# 0SC_praca_mgr.net
KiCad netlist of a schematic drawn in Altium Designer
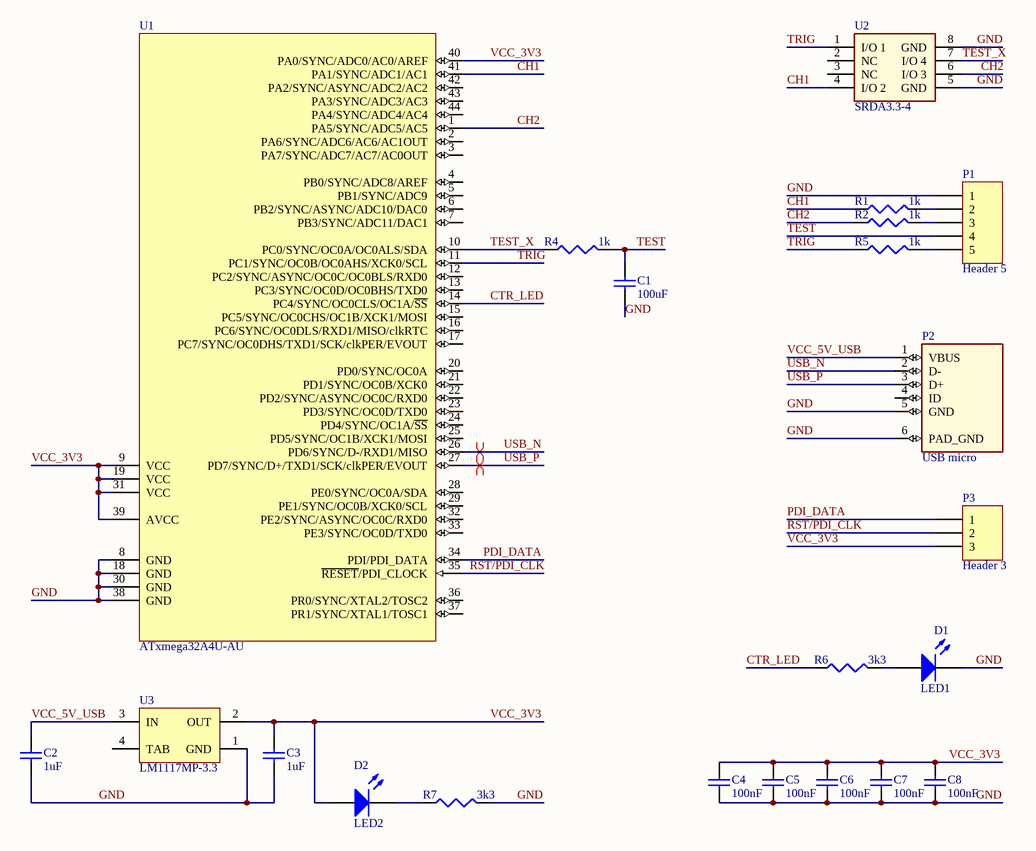
[diagram p0: 0SC_praca_mgr.SchDoc]

(export (version "E")
  (design (tool "Eeschema 10.0.6"))
  (components
    (comp (ref "C1")
      (value "100uF")
      (footprint "1608[0603]")
      (description "Capacitor (Semiconductor SIM Model)")
      (fields (field (name "Comment") "Cap Semi") (field (name "PUBLISHER") "Altium Limited"))
      (libsource (lib "Miscellaneous Devices") (part "Cap Semi"))
    )
    (comp (ref "C2")
      (value "1uF")
      (footprint "1608[0603]")
      (description "Capacitor (Semiconductor SIM Model)")
      (fields (field (name "Comment") "Cap Semi") (field (name "PUBLISHER") "Altium Limited"))
      (libsource (lib "Miscellaneous Devices") (part "Cap Semi"))
    )
    (comp (ref "C3")
      (value "1uF")
      (footprint "1608[0603]")
      (description "Capacitor (Semiconductor SIM Model)")
      (fields (field (name "Comment") "Cap Semi") (field (name "PUBLISHER") "Altium Limited"))
      (libsource (lib "Miscellaneous Devices") (part "Cap Semi"))
    )
    (comp (ref "C4")
      (value "100nF")
      (footprint "1608[0603]")
      (description "Capacitor (Semiconductor SIM Model)")
      (fields (field (name "Comment") "Cap Semi") (field (name "PUBLISHER") "Altium Limited"))
      (libsource (lib "Miscellaneous Devices") (part "Cap Semi"))
    )
    (comp (ref "C5")
      (value "100nF")
      (footprint "1608[0603]")
      (description "Capacitor (Semiconductor SIM Model)")
      (fields (field (name "Comment") "Cap Semi") (field (name "PUBLISHER") "Altium Limited"))
      (libsource (lib "Miscellaneous Devices") (part "Cap Semi"))
    )
    (comp (ref "C6")
      (value "100nF")
      (footprint "1608[0603]")
      (description "Capacitor (Semiconductor SIM Model)")
      (fields (field (name "Comment") "Cap Semi") (field (name "PUBLISHER") "Altium Limited"))
      (libsource (lib "Miscellaneous Devices") (part "Cap Semi"))
    )
    (comp (ref "C7")
      (value "100nF")
      (footprint "1608[0603]")
      (description "Capacitor (Semiconductor SIM Model)")
      (fields (field (name "Comment") "Cap Semi") (field (name "PUBLISHER") "Altium Limited"))
      (libsource (lib "Miscellaneous Devices") (part "Cap Semi"))
    )
    (comp (ref "C8")
      (value "100nF")
      (footprint "1608[0603]")
      (description "Capacitor (Semiconductor SIM Model)")
      (fields (field (name "Comment") "Cap Semi") (field (name "PUBLISHER") "Altium Limited"))
      (libsource (lib "Miscellaneous Devices") (part "Cap Semi"))
    )
    (comp (ref "D1") (value "LED1") (footprint "0603_led") (libsource (lib "Osc_praca_mgr_lib") (part "Led")))
    (comp (ref "D2") (value "LED2") (footprint "0603_led") (libsource (lib "Osc_praca_mgr_lib") (part "Led")))
    (comp (ref "P1")
      (value "Header 5")
      (footprint "HDR1X5")
      (description "Header, 5-Pin")
      (fields (field (name "PUBLISHER") "Altium Limited"))
      (libsource (lib "Miscellaneous Connectors") (part "Header 5"))
    )
    (comp (ref "P2")
      (value "USB micro")
      (footprint "KEY-940")
      (libsource (lib "Osc_praca_mgr_lib") (part "USB micro"))
    )
    (comp (ref "P3")
      (value "Header 3")
      (footprint "HDR1X3")
      (description "Header, 3-Pin")
      (fields (field (name "PUBLISHER") "Altium Limited"))
      (libsource (lib "Miscellaneous Connectors") (part "Header 3"))
    )
    (comp (ref "R1")
      (value "1k")
      (footprint "J1-0603")
      (description "Resistor")
      (fields (field (name "Comment") "Res3") (field (name "PUBLISHER") "Altium Limited"))
      (libsource (lib "Miscellaneous Devices") (part "Res3"))
    )
    (comp (ref "R2")
      (value "1k")
      (footprint "J1-0603")
      (description "Resistor")
      (fields (field (name "Comment") "Res3") (field (name "PUBLISHER") "Altium Limited"))
      (libsource (lib "Miscellaneous Devices") (part "Res3"))
    )
    (comp (ref "R4")
      (value "1k")
      (footprint "J1-0603")
      (description "Resistor")
      (fields (field (name "Comment") "Res3") (field (name "PUBLISHER") "Altium Limited"))
      (libsource (lib "Miscellaneous Devices") (part "Res3"))
    )
    (comp (ref "R5")
      (value "1k")
      (footprint "J1-0603")
      (description "Resistor")
      (fields (field (name "Comment") "Res3") (field (name "PUBLISHER") "Altium Limited"))
      (libsource (lib "Miscellaneous Devices") (part "Res3"))
    )
    (comp (ref "R6")
      (value "3k3")
      (footprint "J1-0603")
      (description "Resistor")
      (fields (field (name "Comment") "Res3") (field (name "PUBLISHER") "Altium Limited"))
      (libsource (lib "Miscellaneous Devices") (part "Res3"))
    )
    (comp (ref "R7")
      (value "3k3")
      (footprint "J1-0603")
      (description "Resistor")
      (fields (field (name "Comment") "Res3") (field (name "PUBLISHER") "Altium Limited"))
      (libsource (lib "Miscellaneous Devices") (part "Res3"))
    )
    (comp (ref "U1")
      (value "ATxmega32A4U-AU")
      (footprint "44A_N")
      (libsource (lib "Atmel Microcontroller AVR XMEGA") (part "ATxmega32A4U-AU"))
    )
    (comp (ref "U2")
      (value "SRDA3.3-4")
      (footprint "SOIC8")
      (libsource (lib "Osc_praca_mgr_lib") (part "SRDA3.3-4"))
    )
    (comp (ref "U3")
      (value "LM1117MP-3.3")
      (footprint "MP04A_N")
      (description "800mA Low-Dropout Linear Regulator")
      (fields
        (field (name "MANUFACTURER") "National Semiconductor")
        (field (name "DIGIKEYPARTNUMBER") "LM1117MP-3.3CT-ND")
        (field (name "PUBLISHER") "Altium Limited")
      )
      (libsource (lib "NSC LDO") (part "LM1117MP-3.3"))
    )
  )
  (nets
    (net (code "1") (name "/CH1") (class "Default")
      (node (ref "R1") (pin "1") (pinfunction "1_1") (pintype "passive"))
      (node (ref "U1") (pin "41") (pinfunction "PA1/SYNC/ADC1/AC1_41") (pintype "bidirectional"))
      (node (ref "U2") (pin "4") (pinfunction "I/O_2_4") (pintype "passive"))
    )
    (net (code "2") (name "/CH2") (class "Default")
      (node (ref "R2") (pin "1") (pinfunction "1_1") (pintype "passive"))
      (node (ref "U1") (pin "1") (pinfunction "PA5/SYNC/ADC5/AC5_1") (pintype "bidirectional"))
      (node (ref "U2") (pin "6") (pinfunction "I/O_3_6") (pintype "passive"))
    )
    (net (code "3") (name "/CTR_LED") (class "Default")
      (node (ref "R6") (pin "1") (pinfunction "1_1") (pintype "passive"))
      (node (ref "U1") (pin "14") (pinfunction "PC4/SYNC/OC0CLS/OC1A/~{SS}_14") (pintype "bidirectional"))
    )
    (net (code "4") (name "/GND") (class "Default")
      (node (ref "C1") (pin "1") (pinfunction "1_1") (pintype "passive"))
      (node (ref "C2") (pin "1") (pinfunction "1_1") (pintype "passive"))
      (node (ref "C3") (pin "1") (pinfunction "1_1") (pintype "passive"))
      (node (ref "C4") (pin "1") (pinfunction "1_1") (pintype "passive"))
      (node (ref "C5") (pin "1") (pinfunction "1_1") (pintype "passive"))
      (node (ref "C6") (pin "1") (pinfunction "1_1") (pintype "passive"))
      (node (ref "C7") (pin "1") (pinfunction "1_1") (pintype "passive"))
      (node (ref "C8") (pin "1") (pinfunction "1_1") (pintype "passive"))
      (node (ref "D1") (pin "2") (pinfunction "K_2") (pintype "passive"))
      (node (ref "P1") (pin "1") (pinfunction "1_1") (pintype "passive"))
      (node (ref "P2") (pin "5") (pinfunction "GND_5") (pintype "bidirectional"))
      (node (ref "P2") (pin "6") (pinfunction "PAD_GND_6") (pintype "bidirectional"))
      (node (ref "R7") (pin "2") (pinfunction "2_2") (pintype "passive"))
      (node (ref "U1") (pin "18") (pinfunction "GND_18") (pintype "power_in"))
      (node (ref "U1") (pin "30") (pinfunction "GND_30") (pintype "power_in"))
      (node (ref "U1") (pin "38") (pinfunction "GND_38") (pintype "power_in"))
      (node (ref "U1") (pin "8") (pinfunction "GND_8") (pintype "power_in"))
      (node (ref "U2") (pin "5") (pinfunction "GND_5") (pintype "passive"))
      (node (ref "U2") (pin "8") (pinfunction "GND_8") (pintype "passive"))
      (node (ref "U3") (pin "1") (pinfunction "GND_1") (pintype "power_in"))
    )
    (net (code "5") (name "/PDI_DATA") (class "Default")
      (node (ref "P3") (pin "1") (pinfunction "1_1") (pintype "passive"))
      (node (ref "U1") (pin "34") (pinfunction "PDI/PDI_DATA_34") (pintype "bidirectional"))
    )
    (net (code "6") (name "/TEST") (class "Default")
      (node (ref "C1") (pin "2") (pinfunction "2_2") (pintype "passive"))
      (node (ref "P1") (pin "4") (pinfunction "4_4") (pintype "passive"))
      (node (ref "R4") (pin "2") (pinfunction "2_2") (pintype "passive"))
    )
    (net (code "7") (name "/TEST_X") (class "Default")
      (node (ref "R4") (pin "1") (pinfunction "1_1") (pintype "passive"))
      (node (ref "U1") (pin "10") (pinfunction "PC0/SYNC/OC0A/OC0ALS/SDA_10") (pintype "bidirectional"))
      (node (ref "U2") (pin "7") (pinfunction "I/O_4_7") (pintype "passive"))
    )
    (net (code "8") (name "/TRIG") (class "Default")
      (node (ref "R5") (pin "1") (pinfunction "1_1") (pintype "passive"))
      (node (ref "U1") (pin "11") (pinfunction "PC1/SYNC/OC0B/OC0AHS/XCK0/SCL_11") (pintype "bidirectional"))
      (node (ref "U2") (pin "1") (pinfunction "I/O_1_1") (pintype "passive"))
    )
    (net (code "9") (name "/USB_N") (class "Default")
      (node (ref "P2") (pin "2") (pinfunction "D-_2") (pintype "bidirectional"))
      (node (ref "U1") (pin "26") (pinfunction "PD6/SYNC/D-/RXD1/MISO_26") (pintype "bidirectional"))
    )
    (net (code "10") (name "/USB_P") (class "Default")
      (node (ref "P2") (pin "3") (pinfunction "D+_3") (pintype "bidirectional"))
      (node (ref "U1") (pin "27") (pinfunction "PD7/SYNC/D+/TXD1/SCK/clkPER/EVOUT_27") (pintype "bidirectional"))
    )
    (net (code "11") (name "/VCC_3V3") (class "Default")
      (node (ref "C3") (pin "2") (pinfunction "2_2") (pintype "passive"))
      (node (ref "C4") (pin "2") (pinfunction "2_2") (pintype "passive"))
      (node (ref "C5") (pin "2") (pinfunction "2_2") (pintype "passive"))
      (node (ref "C6") (pin "2") (pinfunction "2_2") (pintype "passive"))
      (node (ref "C7") (pin "2") (pinfunction "2_2") (pintype "passive"))
      (node (ref "C8") (pin "2") (pinfunction "2_2") (pintype "passive"))
      (node (ref "D2") (pin "1") (pinfunction "A_1") (pintype "passive"))
      (node (ref "P3") (pin "3") (pinfunction "3_3") (pintype "passive"))
      (node (ref "U1") (pin "19") (pinfunction "VCC_19") (pintype "power_in"))
      (node (ref "U1") (pin "31") (pinfunction "VCC_31") (pintype "power_in"))
      (node (ref "U1") (pin "39") (pinfunction "AVCC_39") (pintype "power_in"))
      (node (ref "U1") (pin "40") (pinfunction "PA0/SYNC/ADC0/AC0/AREF_40") (pintype "bidirectional"))
      (node (ref "U1") (pin "9") (pinfunction "VCC_9") (pintype "power_in"))
      (node (ref "U3") (pin "2") (pinfunction "OUT_2") (pintype "power_in"))
    )
    (net (code "12") (name "/VCC_5V_USB") (class "Default")
      (node (ref "C2") (pin "2") (pinfunction "2_2") (pintype "passive"))
      (node (ref "P2") (pin "1") (pinfunction "VBUS_1") (pintype "bidirectional"))
      (node (ref "U3") (pin "3") (pinfunction "IN_3") (pintype "power_in"))
    )
    (net (code "13") (name "/~{RST}{slash}PDI_CLK") (class "Default")
      (node (ref "P3") (pin "2") (pinfunction "2_2") (pintype "passive"))
      (node (ref "U1") (pin "35") (pinfunction "~{RESET}/PDI_CLOCK_35") (pintype "input"))
    )
    (net (code "14") (name "Net-(D1-A)") (class "Default")
      (node (ref "D1") (pin "1") (pinfunction "A_1") (pintype "passive"))
      (node (ref "R6") (pin "2") (pinfunction "2_2") (pintype "passive"))
    )
    (net (code "15") (name "Net-(D2-K)") (class "Default")
      (node (ref "D2") (pin "2") (pinfunction "K_2") (pintype "passive"))
      (node (ref "R7") (pin "1") (pinfunction "1_1") (pintype "passive"))
    )
    (net (code "16") (name "Net-(P1-Pad2)") (class "Default")
      (node (ref "P1") (pin "2") (pinfunction "2_2") (pintype "passive"))
      (node (ref "R1") (pin "2") (pinfunction "2_2") (pintype "passive"))
    )
    (net (code "17") (name "Net-(P1-Pad3)") (class "Default")
      (node (ref "P1") (pin "3") (pinfunction "3_3") (pintype "passive"))
      (node (ref "R2") (pin "2") (pinfunction "2_2") (pintype "passive"))
    )
    (net (code "18") (name "Net-(P1-Pad5)") (class "Default")
      (node (ref "P1") (pin "5") (pinfunction "5_5") (pintype "passive"))
      (node (ref "R5") (pin "2") (pinfunction "2_2") (pintype "passive"))
    )
    (net (code "19") (name "unconnected-(P2-ID-Pad4)") (class "Default")
      (node (ref "P2") (pin "4") (pinfunction "ID_4") (pintype "bidirectional"))
    )
    (net (code "20") (name "unconnected-(U1-PA2{slash}SYNC{slash}ASYNC{slash}ADC2{slash}AC2-Pad42)") (class "Default")
      (node (ref "U1") (pin "42") (pinfunction "PA2/SYNC/ASYNC/ADC2/AC2_42") (pintype "bidirectional"))
    )
    (net (code "21") (name "unconnected-(U1-PA3{slash}SYNC{slash}ADC3{slash}AC3-Pad43)") (class "Default")
      (node (ref "U1") (pin "43") (pinfunction "PA3/SYNC/ADC3/AC3_43") (pintype "bidirectional"))
    )
    (net (code "22") (name "unconnected-(U1-PA4{slash}SYNC{slash}ADC4{slash}AC4-Pad44)") (class "Default")
      (node (ref "U1") (pin "44") (pinfunction "PA4/SYNC/ADC4/AC4_44") (pintype "bidirectional"))
    )
    (net (code "23") (name "unconnected-(U1-PA6{slash}SYNC{slash}ADC6{slash}AC6{slash}AC1OUT-Pad2)") (class "Default")
      (node (ref "U1") (pin "2") (pinfunction "PA6/SYNC/ADC6/AC6/AC1OUT_2") (pintype "bidirectional"))
    )
    (net (code "24") (name "unconnected-(U1-PA7{slash}SYNC{slash}ADC7{slash}AC7{slash}AC0OUT-Pad3)") (class "Default")
      (node (ref "U1") (pin "3") (pinfunction "PA7/SYNC/ADC7/AC7/AC0OUT_3") (pintype "bidirectional"))
    )
    (net (code "25") (name "unconnected-(U1-PB0{slash}SYNC{slash}ADC8{slash}AREF-Pad4)") (class "Default")
      (node (ref "U1") (pin "4") (pinfunction "PB0/SYNC/ADC8/AREF_4") (pintype "bidirectional"))
    )
    (net (code "26") (name "unconnected-(U1-PB1{slash}SYNC{slash}ADC9-Pad5)") (class "Default")
      (node (ref "U1") (pin "5") (pinfunction "PB1/SYNC/ADC9_5") (pintype "bidirectional"))
    )
    (net (code "27") (name "unconnected-(U1-PB2{slash}SYNC{slash}ASYNC{slash}ADC10{slash}DAC0-Pad6)") (class "Default")
      (node (ref "U1") (pin "6") (pinfunction "PB2/SYNC/ASYNC/ADC10/DAC0_6") (pintype "bidirectional"))
    )
    (net (code "28") (name "unconnected-(U1-PB3{slash}SYNC{slash}ADC11{slash}DAC1-Pad7)") (class "Default")
      (node (ref "U1") (pin "7") (pinfunction "PB3/SYNC/ADC11/DAC1_7") (pintype "bidirectional"))
    )
    (net (code "29") (name "unconnected-(U1-PC2{slash}SYNC{slash}ASYNC{slash}OC0C{slash}OC0BLS{slash}RXD0-Pad12)") (class "Default")
      (node (ref "U1") (pin "12") (pinfunction "PC2/SYNC/ASYNC/OC0C/OC0BLS/RXD0_12") (pintype "bidirectional"))
    )
    (net (code "30") (name "unconnected-(U1-PC3{slash}SYNC{slash}OC0D{slash}OC0BHS{slash}TXD0-Pad13)") (class "Default")
      (node (ref "U1") (pin "13") (pinfunction "PC3/SYNC/OC0D/OC0BHS/TXD0_13") (pintype "bidirectional"))
    )
    (net (code "31") (name "unconnected-(U1-PC5{slash}SYNC{slash}OC0CHS{slash}OC1B{slash}XCK1{slash}MOSI-Pad15)") (class "Default")
      (node (ref "U1") (pin "15") (pinfunction "PC5/SYNC/OC0CHS/OC1B/XCK1/MOSI_15") (pintype "bidirectional"))
    )
    (net (code "32") (name "unconnected-(U1-PC6{slash}SYNC{slash}OC0DLS{slash}RXD1{slash}MISO{slash}clkRTC-Pad16)") (class "Default")
      (node (ref "U1") (pin "16") (pinfunction "PC6/SYNC/OC0DLS/RXD1/MISO/clkRTC_16") (pintype "bidirectional"))
    )
    (net (code "33") (name "unconnected-(U1-PC7{slash}SYNC{slash}OC0DHS{slash}TXD1{slash}SCK{slash}clkPER{slash}EVOUT-Pad17)") (class "Default")
      (node (ref "U1") (pin "17") (pinfunction "PC7/SYNC/OC0DHS/TXD1/SCK/clkPER/EVOUT_17") (pintype "bidirectional"))
    )
    (net (code "34") (name "unconnected-(U1-PD0{slash}SYNC{slash}OC0A-Pad20)") (class "Default")
      (node (ref "U1") (pin "20") (pinfunction "PD0/SYNC/OC0A_20") (pintype "bidirectional"))
    )
    (net (code "35") (name "unconnected-(U1-PD1{slash}SYNC{slash}OC0B{slash}XCK0-Pad21)") (class "Default")
      (node (ref "U1") (pin "21") (pinfunction "PD1/SYNC/OC0B/XCK0_21") (pintype "bidirectional"))
    )
    (net (code "36") (name "unconnected-(U1-PD2{slash}SYNC{slash}ASYNC{slash}OC0C{slash}RXD0-Pad22)") (class "Default")
      (node (ref "U1") (pin "22") (pinfunction "PD2/SYNC/ASYNC/OC0C/RXD0_22") (pintype "bidirectional"))
    )
    (net (code "37") (name "unconnected-(U1-PD3{slash}SYNC{slash}OC0D{slash}TXD0-Pad23)") (class "Default")
      (node (ref "U1") (pin "23") (pinfunction "PD3/SYNC/OC0D/TXD0_23") (pintype "bidirectional"))
    )
    (net (code "38") (name "unconnected-(U1-PD4{slash}SYNC{slash}OC1A{slash}~{SS}-Pad24)") (class "Default")
      (node (ref "U1") (pin "24") (pinfunction "PD4/SYNC/OC1A/~{SS}_24") (pintype "bidirectional"))
    )
    (net (code "39") (name "unconnected-(U1-PD5{slash}SYNC{slash}OC1B{slash}XCK1{slash}MOSI-Pad25)") (class "Default")
      (node (ref "U1") (pin "25") (pinfunction "PD5/SYNC/OC1B/XCK1/MOSI_25") (pintype "bidirectional"))
    )
    (net (code "40") (name "unconnected-(U1-PE0{slash}SYNC{slash}OC0A{slash}SDA-Pad28)") (class "Default")
      (node (ref "U1") (pin "28") (pinfunction "PE0/SYNC/OC0A/SDA_28") (pintype "bidirectional"))
    )
    (net (code "41") (name "unconnected-(U1-PE1{slash}SYNC{slash}OC0B{slash}XCK0{slash}SCL-Pad29)") (class "Default")
      (node (ref "U1") (pin "29") (pinfunction "PE1/SYNC/OC0B/XCK0/SCL_29") (pintype "bidirectional"))
    )
    (net (code "42") (name "unconnected-(U1-PE2{slash}SYNC{slash}ASYNC{slash}OC0C{slash}RXD0-Pad32)") (class "Default")
      (node (ref "U1") (pin "32") (pinfunction "PE2/SYNC/ASYNC/OC0C/RXD0_32") (pintype "bidirectional"))
    )
    (net (code "43") (name "unconnected-(U1-PE3{slash}SYNC{slash}OC0D{slash}TXD0-Pad33)") (class "Default")
      (node (ref "U1") (pin "33") (pinfunction "PE3/SYNC/OC0D/TXD0_33") (pintype "bidirectional"))
    )
    (net (code "44") (name "unconnected-(U1-PR0{slash}SYNC{slash}XTAL2{slash}TOSC2-Pad36)") (class "Default")
      (node (ref "U1") (pin "36") (pinfunction "PR0/SYNC/XTAL2/TOSC2_36") (pintype "bidirectional"))
    )
    (net (code "45") (name "unconnected-(U1-PR1{slash}SYNC{slash}XTAL1{slash}TOSC1-Pad37)") (class "Default")
      (node (ref "U1") (pin "37") (pinfunction "PR1/SYNC/XTAL1/TOSC1_37") (pintype "bidirectional"))
    )
    (net (code "46") (name "unconnected-(U2-NC-Pad2)") (class "Default")
      (node (ref "U2") (pin "2") (pinfunction "NC_2") (pintype "passive"))
    )
    (net (code "47") (name "unconnected-(U2-NC-Pad3)") (class "Default")
      (node (ref "U2") (pin "3") (pinfunction "NC_3") (pintype "passive"))
    )
    (net (code "48") (name "unconnected-(U3-TAB-Pad4)") (class "Default")
      (node (ref "U3") (pin "4") (pinfunction "TAB_4") (pintype "power_in"))
    )
  )
)
